# Schematic.net
KiCad netlist of a schematic drawn in EasyEDA
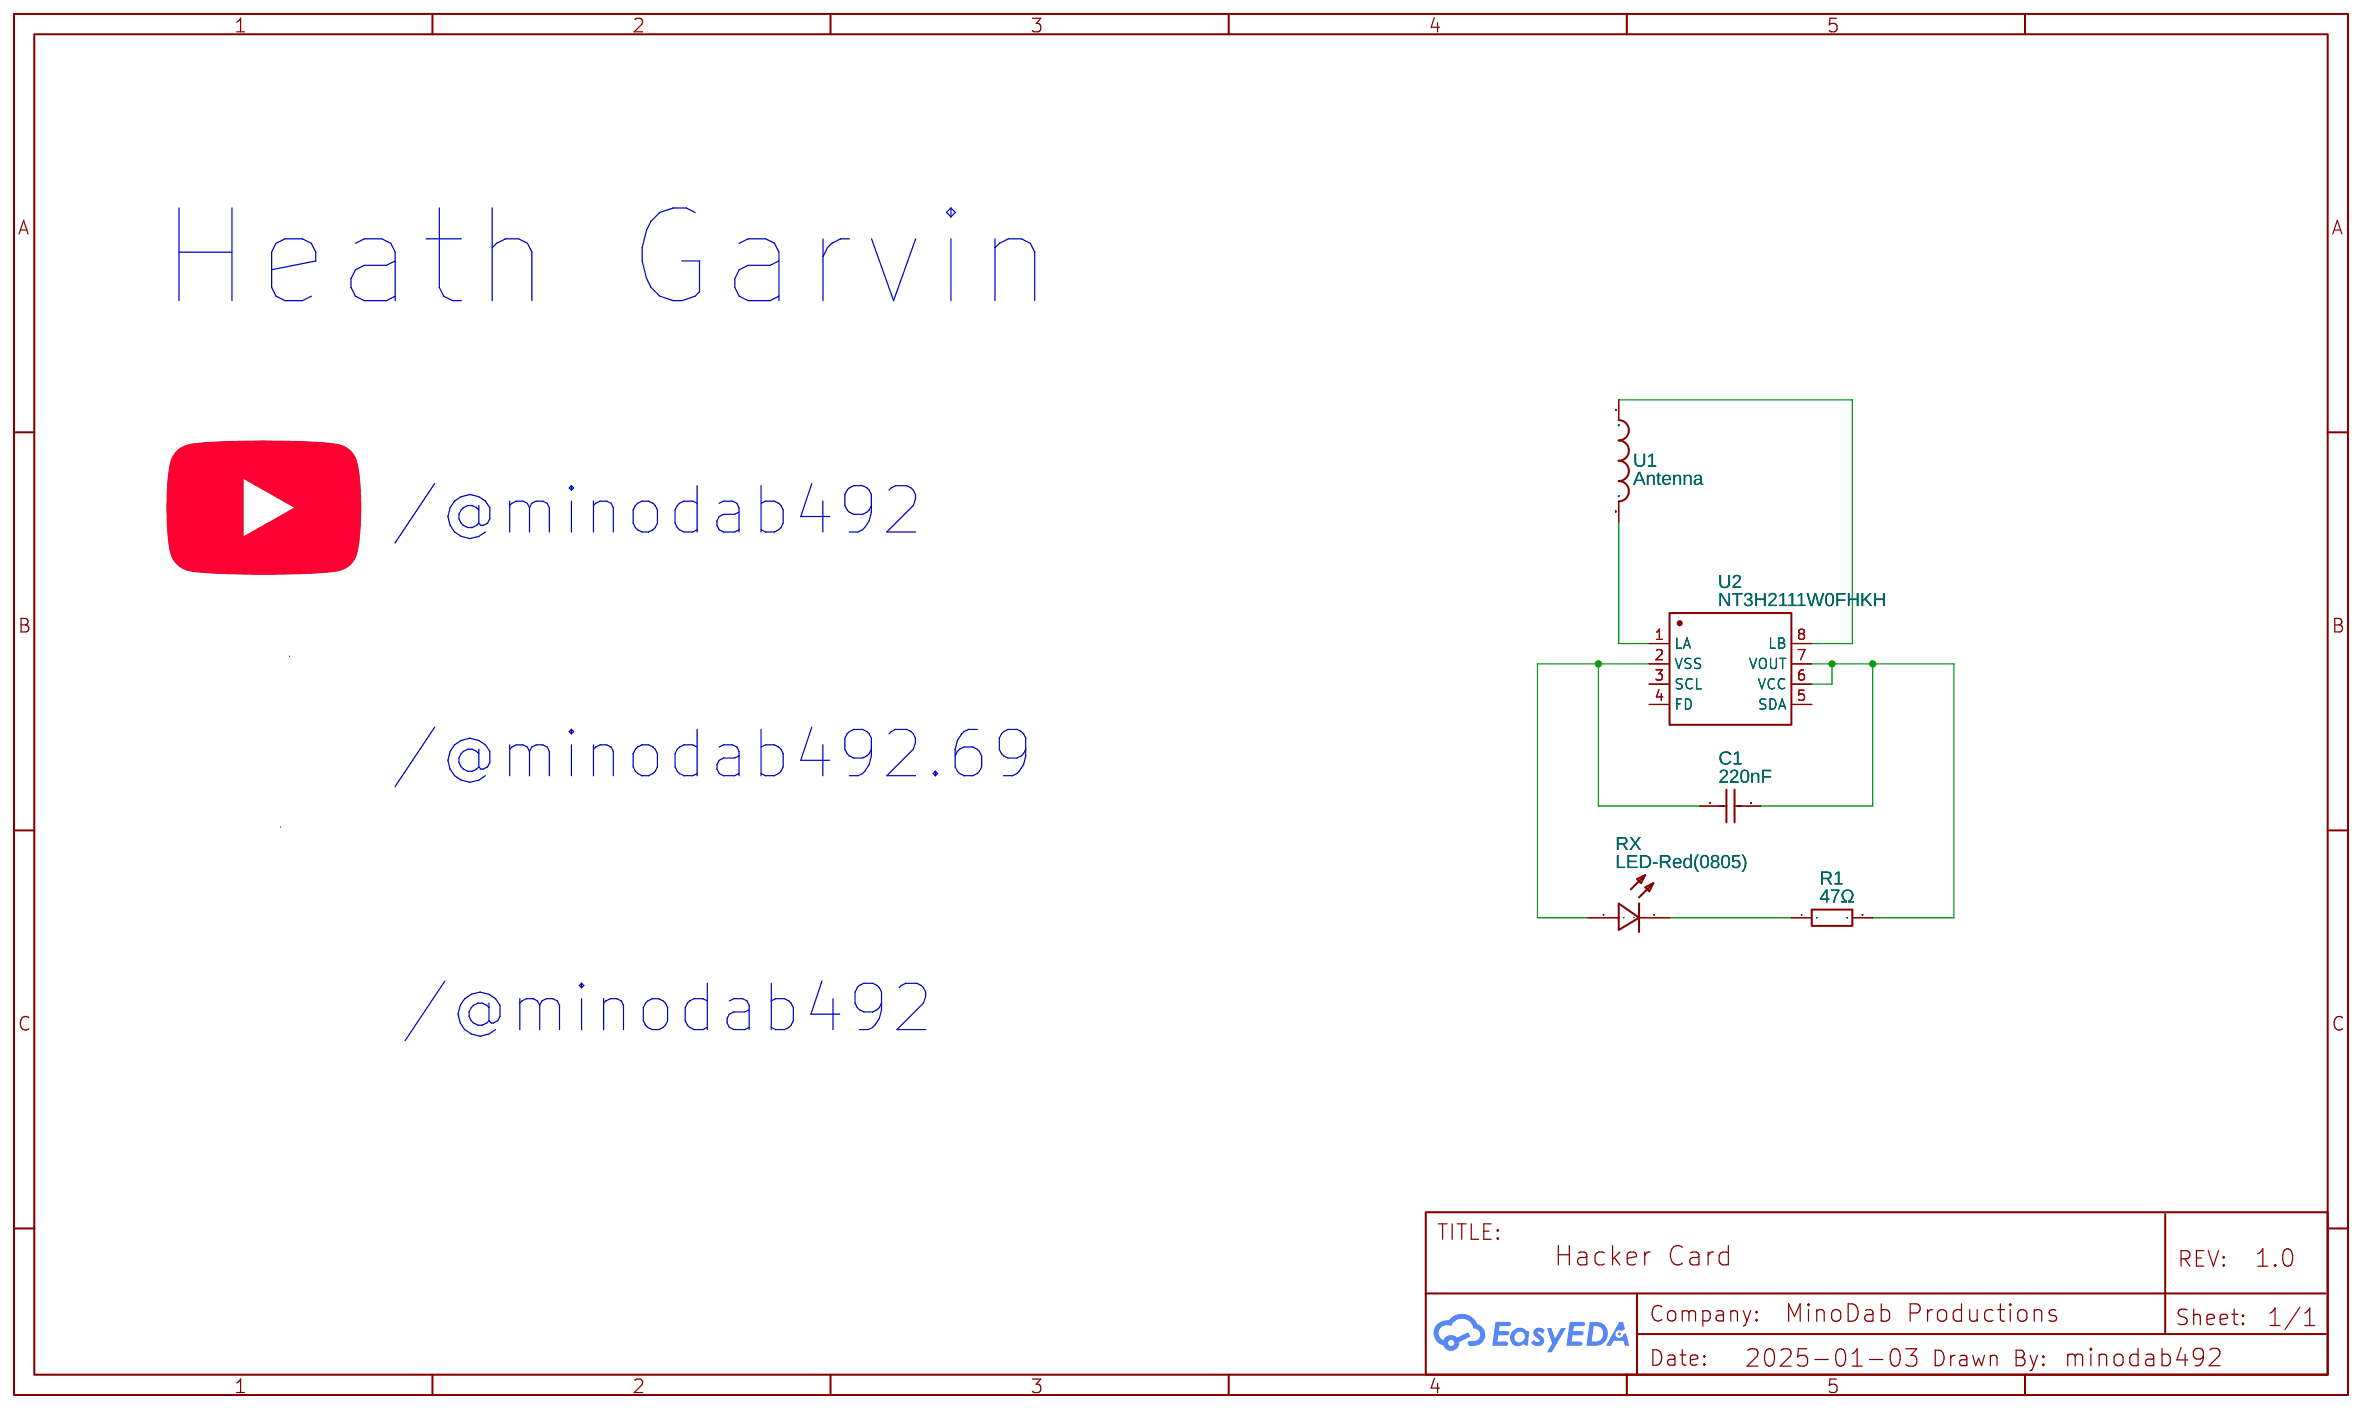
[diagram p0: schematic sheet]

(export (version "E")
  (design (tool "Eeschema 10.0.6"))
  (components
    (comp (ref "C1")
      (value "220nF")
      (fields
        (field (name "Manufacturer Part") "CL10B224KA8NNNC")
        (field (name "Manufacturer") "SAMSUNG(三星)")
      )
      (libsource (lib "") (part "CL10B224KA8NNNC"))
    )
    (comp (ref "R1")
      (value "47Ω")
      (fields
        (field (name "Manufacturer Part") "0603WAF470JT5E")
        (field (name "Manufacturer") "UNI-ROYAL(厚声)")
      )
      (libsource (lib "") (part "0603WAF470JT5E"))
    )
    (comp (ref "RX")
      (value "LED-Red(0805)")
      (fields
        (field (name "Manufacturer Part") "17-21SUYC/TR8")
        (field (name "Manufacturer") "Hubei KENTO Elec")
      )
      (libsource (lib "") (part "LED-Red(0805)"))
    )
    (comp (ref "U1") (value "Antenna") (libsource (lib "") (part "Antenna")))
    (comp (ref "U2")
      (value "NT3H2111W0FHKH")
      (fields (field (name "Manufacturer") "NXP(恩智浦)"))
      (libsource (lib "") (part "NT3H2111W0FHKH"))
    )
  )
  (nets
    (net (code "1") (name "Net-(RX-+)") (class "Default")
      (node (ref "C1") (pin "1") (pinfunction "1_1") (pintype "input"))
      (node (ref "RX") (pin "1") (pinfunction "+_1") (pintype "unspecified"))
      (node (ref "U2") (pin "2") (pinfunction "VSS_2") (pintype "unspecified"))
    )
    (net (code "2") (name "Net-(RX--)") (class "Default")
      (node (ref "R1") (pin "1") (pinfunction "1_1") (pintype "input"))
      (node (ref "RX") (pin "2") (pinfunction "-_2") (pintype "unspecified"))
    )
    (net (code "3") (name "Net-(U2-LA)") (class "Default")
      (node (ref "U1") (pin "P$1") (pinfunction "P$1_P$1") (pintype "unspecified"))
      (node (ref "U2") (pin "1") (pinfunction "LA_1") (pintype "unspecified"))
    )
    (net (code "4") (name "Net-(U2-LB)") (class "Default")
      (node (ref "U1") (pin "P$2") (pinfunction "P$2_P$2") (pintype "unspecified"))
      (node (ref "U2") (pin "8") (pinfunction "LB_8") (pintype "unspecified"))
    )
    (net (code "5") (name "Net-(U2-VCC)") (class "Default")
      (node (ref "C1") (pin "2") (pinfunction "2_2") (pintype "input"))
      (node (ref "R1") (pin "2") (pinfunction "2_2") (pintype "input"))
      (node (ref "U2") (pin "6") (pinfunction "VCC_6") (pintype "unspecified"))
      (node (ref "U2") (pin "7") (pinfunction "VOUT_7") (pintype "unspecified"))
    )
    (net (code "6") (name "unconnected-(U2-FD-Pad4)") (class "Default")
      (node (ref "U2") (pin "4") (pinfunction "FD_4") (pintype "unspecified"))
    )
    (net (code "7") (name "unconnected-(U2-SCL-Pad3)") (class "Default")
      (node (ref "U2") (pin "3") (pinfunction "SCL_3") (pintype "unspecified"))
    )
    (net (code "8") (name "unconnected-(U2-SDA-Pad5)") (class "Default")
      (node (ref "U2") (pin "5") (pinfunction "SDA_5") (pintype "unspecified"))
    )
  )
)
